# USB_Micro_B.net
KiCad netlist of a schematic drawn in EAGLE
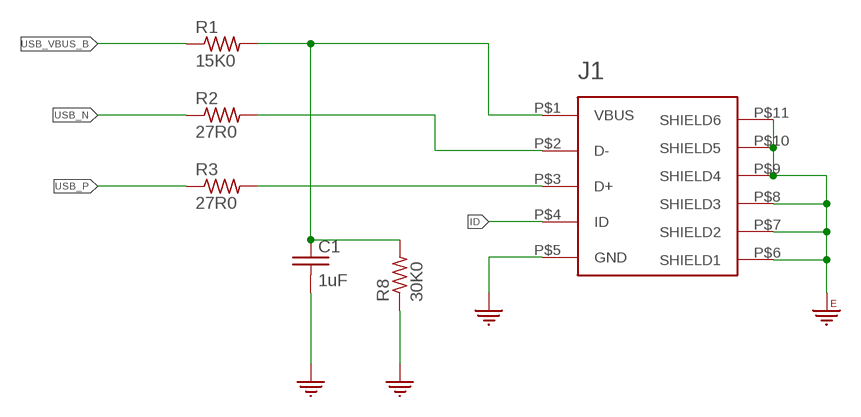
[diagram p0: schematic, sheet 1]

(export (version "E")
  (design (tool "Eeschema 10.0.6"))
  (components
    (comp (ref "C1")
      (value "1uF")
      (footprint "eagle-import:0402")
      (libsource (lib "eagle-import") (part "C_0402"))
    )
    (comp (ref "J1")
      (value "USB-B-Micro")
      (footprint "eagle-import:USB_MICRO-B")
      (fields (field (name "PARTNO") "10118192-0002LF"))
      (libsource (lib "eagle-import") (part "USB_MICRO-B"))
    )
    (comp (ref "R1")
      (value "15K0")
      (footprint "eagle-import:0402")
      (libsource (lib "eagle-import") (part "R_0402"))
    )
    (comp (ref "R2")
      (value "27R0")
      (footprint "eagle-import:0402")
      (libsource (lib "eagle-import") (part "R_0402"))
    )
    (comp (ref "R3")
      (value "27R0")
      (footprint "eagle-import:0402")
      (libsource (lib "eagle-import") (part "R_0402"))
    )
    (comp (ref "R8")
      (value "30K0")
      (footprint "eagle-import:0402")
      (libsource (lib "eagle-import") (part "R_0402"))
    )
  )
  (nets
    (net (code "1") (name "GND") (class "Default")
      (node (ref "C1") (pin "2") (pinfunction "2_2") (pintype "passive"))
      (node (ref "J1") (pin "P$5") (pinfunction "GND_P$5") (pintype "bidirectional"))
      (node (ref "R8") (pin "1") (pinfunction "1_1") (pintype "passive"))
    )
    (net (code "2") (name "GNDEARTH") (class "Default")
      (node (ref "J1") (pin "P$10") (pinfunction "SHIELD5_P$10") (pintype "bidirectional"))
      (node (ref "J1") (pin "P$11") (pinfunction "SHIELD6_P$11") (pintype "bidirectional"))
      (node (ref "J1") (pin "P$6") (pinfunction "SHIELD1_P$6") (pintype "bidirectional"))
      (node (ref "J1") (pin "P$7") (pinfunction "SHIELD2_P$7") (pintype "bidirectional"))
      (node (ref "J1") (pin "P$8") (pinfunction "SHIELD3_P$8") (pintype "bidirectional"))
      (node (ref "J1") (pin "P$9") (pinfunction "SHIELD4_P$9") (pintype "bidirectional"))
    )
    (net (code "3") (name "ID") (class "Default")
      (node (ref "J1") (pin "P$4") (pinfunction "ID_P$4") (pintype "bidirectional"))
    )
    (net (code "4") (name "Net-(J1-D+)") (class "Default")
      (node (ref "J1") (pin "P$3") (pinfunction "D+_P$3") (pintype "bidirectional"))
      (node (ref "R3") (pin "2") (pinfunction "2_2") (pintype "passive"))
    )
    (net (code "5") (name "Net-(J1-D-)") (class "Default")
      (node (ref "J1") (pin "P$2") (pinfunction "D-_P$2") (pintype "bidirectional"))
      (node (ref "R2") (pin "2") (pinfunction "2_2") (pintype "passive"))
    )
    (net (code "6") (name "Net-(J1-VBUS)") (class "Default")
      (node (ref "C1") (pin "1") (pinfunction "1_1") (pintype "passive"))
      (node (ref "J1") (pin "P$1") (pinfunction "VBUS_P$1") (pintype "bidirectional"))
      (node (ref "R1") (pin "2") (pinfunction "2_2") (pintype "passive"))
      (node (ref "R8") (pin "2") (pinfunction "2_2") (pintype "passive"))
    )
    (net (code "7") (name "USB_N") (class "Default")
      (node (ref "R2") (pin "1") (pinfunction "1_1") (pintype "passive"))
    )
    (net (code "8") (name "USB_P") (class "Default")
      (node (ref "R3") (pin "1") (pinfunction "1_1") (pintype "passive"))
    )
    (net (code "9") (name "USB_VBUS_B") (class "Default")
      (node (ref "R1") (pin "1") (pinfunction "1_1") (pintype "passive"))
    )
  )
)
